# Schematic_Main_Board_backup.net
KiCad netlist of a schematic drawn in Altium Designer
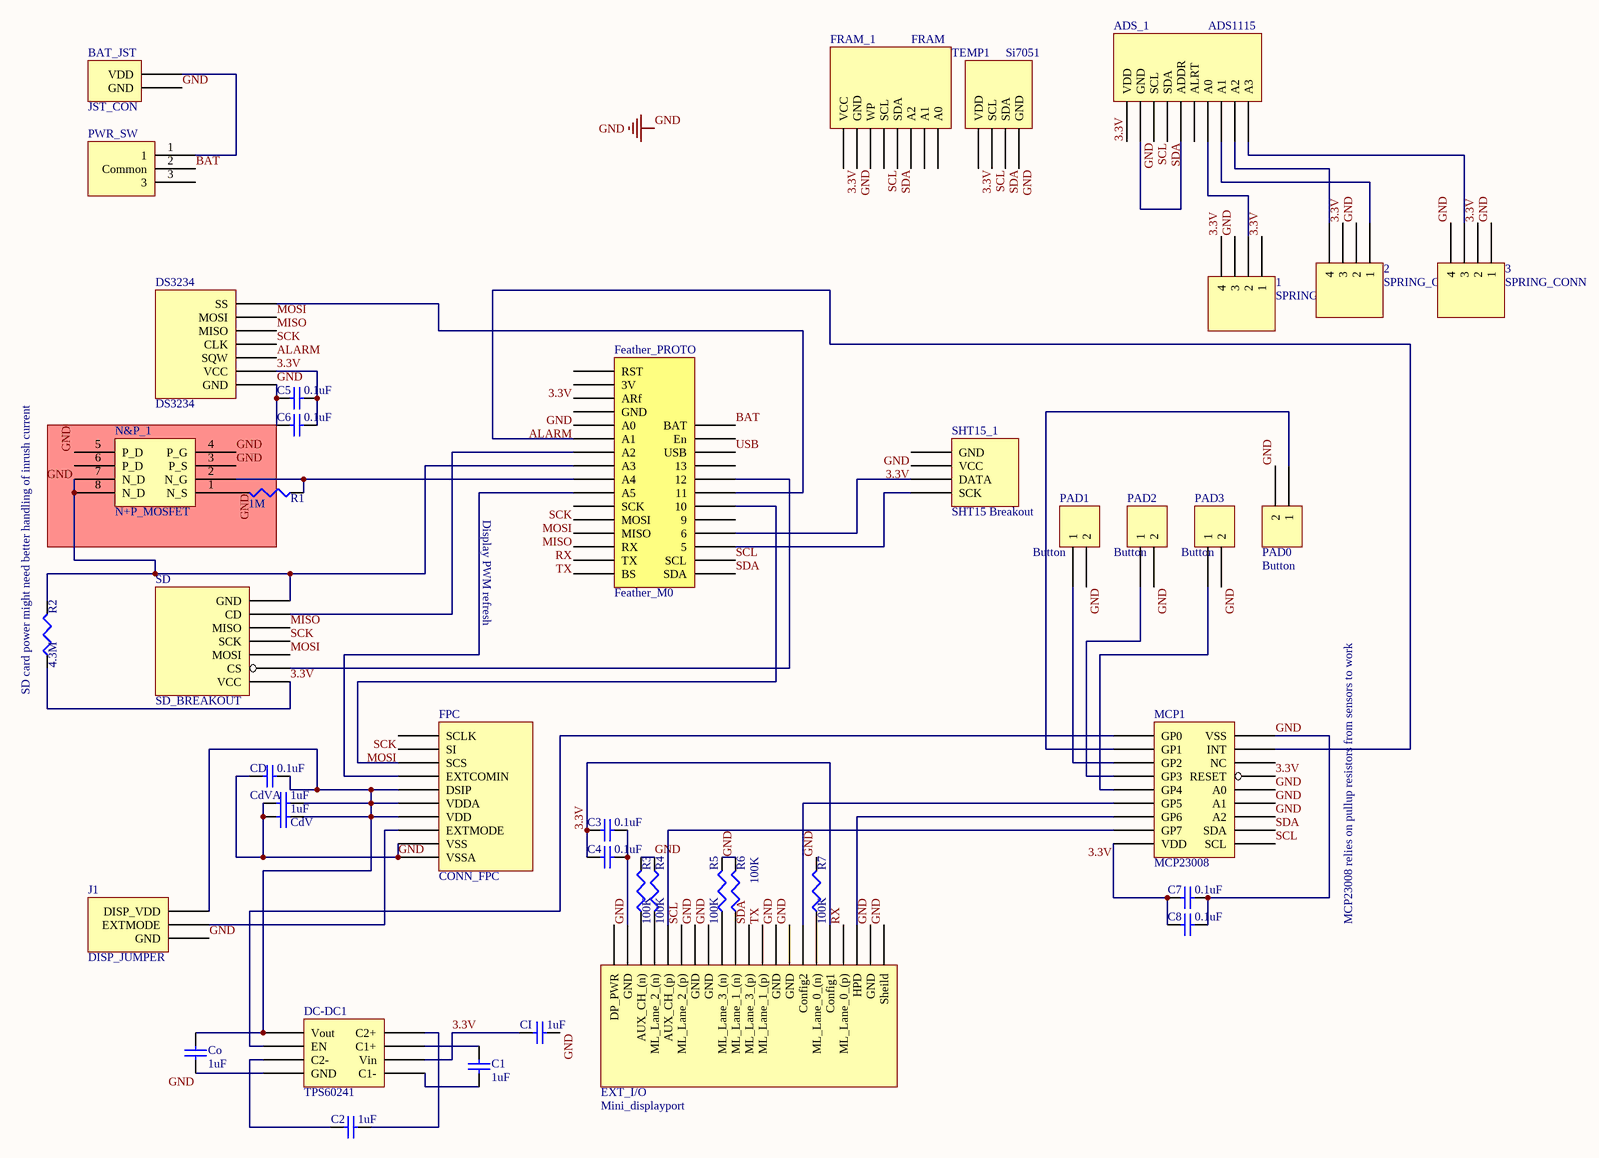
[diagram p0: Schematic_Main_Board_backup.SchDoc]

(export (version "E")
  (design (tool "Eeschema 10.0.6"))
  (components
    (comp (ref "1")
      (value "SPRING_CONN")
      (footprint "QUICK_CONN")
      (libsource (lib "Parts_Schematic") (part "SPRING_CONN"))
    )
    (comp (ref "2")
      (value "SPRING_CONN")
      (footprint "QUICK_CONN")
      (libsource (lib "Parts_Schematic") (part "SPRING_CONN"))
    )
    (comp (ref "3")
      (value "SPRING_CONN")
      (footprint "QUICK_CONN")
      (libsource (lib "Parts_Schematic") (part "SPRING_CONN"))
    )
    (comp (ref "ADS_1")
      (value "ADS1115")
      (footprint "ADS1115")
      (libsource (lib "Parts_Schematic") (part "ADS1115"))
    )
    (comp (ref "BAT_JST")
      (value "JST_CON")
      (footprint "JST_CONN")
      (libsource (lib "Parts_Schematic") (part "JST_CON"))
    )
    (comp (ref "C1")
      (value "1uF")
      (footprint "C0805")
      (description "Capacitor (Semiconductor SIM Model)")
      (fields (field (name "Comment") "Cap Semi") (field (name "PUBLISHER") "Altium Limited"))
      (libsource (lib "Miscellaneous Devices") (part "Cap Semi"))
    )
    (comp (ref "C2")
      (value "1uF")
      (footprint "C0805")
      (description "Capacitor (Semiconductor SIM Model)")
      (fields (field (name "Comment") "Cap Semi") (field (name "PUBLISHER") "Altium Limited"))
      (libsource (lib "Miscellaneous Devices") (part "Cap Semi"))
    )
    (comp (ref "C3")
      (value "0.1uF")
      (footprint "C0805")
      (description "Capacitor (Semiconductor SIM Model)")
      (fields (field (name "Comment") "Cap Semi") (field (name "PUBLISHER") "Altium Limited"))
      (libsource (lib "Miscellaneous Devices") (part "Cap Semi"))
    )
    (comp (ref "C4")
      (value "0.1uF")
      (footprint "C0805")
      (description "Capacitor (Semiconductor SIM Model)")
      (fields (field (name "Comment") "Cap Semi") (field (name "PUBLISHER") "Altium Limited"))
      (libsource (lib "Miscellaneous Devices") (part "Cap Semi"))
    )
    (comp (ref "C5")
      (value "0.1uF")
      (footprint "C0805")
      (description "Capacitor (Semiconductor SIM Model)")
      (fields (field (name "Comment") "Cap Semi") (field (name "PUBLISHER") "Altium Limited"))
      (libsource (lib "Miscellaneous Devices") (part "Cap Semi"))
    )
    (comp (ref "C6")
      (value "0.1uF")
      (footprint "C0805")
      (description "Capacitor (Semiconductor SIM Model)")
      (fields (field (name "Comment") "Cap Semi") (field (name "PUBLISHER") "Altium Limited"))
      (libsource (lib "Miscellaneous Devices") (part "Cap Semi"))
    )
    (comp (ref "C7")
      (value "0.1uF")
      (footprint "C0805")
      (description "Capacitor (Semiconductor SIM Model)")
      (fields (field (name "Comment") "Cap Semi") (field (name "PUBLISHER") "Altium Limited"))
      (libsource (lib "Miscellaneous Devices") (part "Cap Semi"))
    )
    (comp (ref "C8")
      (value "0.1uF")
      (footprint "C0805")
      (description "Capacitor (Semiconductor SIM Model)")
      (fields (field (name "Comment") "Cap Semi") (field (name "PUBLISHER") "Altium Limited"))
      (libsource (lib "Miscellaneous Devices") (part "Cap Semi"))
    )
    (comp (ref "CD")
      (value "0.1uF")
      (footprint "C0805")
      (description "Capacitor (Semiconductor SIM Model)")
      (fields (field (name "Comment") "Cap Semi") (field (name "PUBLISHER") "Altium Limited"))
      (libsource (lib "Miscellaneous Devices") (part "Cap Semi"))
    )
    (comp (ref "CdV")
      (value "1uF")
      (footprint "C0805")
      (description "Capacitor (Semiconductor SIM Model)")
      (fields (field (name "Comment") "Cap Semi") (field (name "PUBLISHER") "Altium Limited"))
      (libsource (lib "Miscellaneous Devices") (part "Cap Semi"))
    )
    (comp (ref "CdVA")
      (value "1uF")
      (footprint "C0805")
      (description "Capacitor (Semiconductor SIM Model)")
      (fields (field (name "Comment") "Cap Semi") (field (name "PUBLISHER") "Altium Limited"))
      (libsource (lib "Miscellaneous Devices") (part "Cap Semi"))
    )
    (comp (ref "CI")
      (value "1uF")
      (footprint "C0805")
      (description "Capacitor (Semiconductor SIM Model)")
      (fields (field (name "Comment") "Cap Semi") (field (name "PUBLISHER") "Altium Limited"))
      (libsource (lib "Miscellaneous Devices") (part "Cap Semi"))
    )
    (comp (ref "Co")
      (value "1uF")
      (footprint "C0805")
      (description "Capacitor (Semiconductor SIM Model)")
      (fields (field (name "Comment") "Cap Semi") (field (name "PUBLISHER") "Altium Limited"))
      (libsource (lib "Miscellaneous Devices") (part "Cap Semi"))
    )
    (comp (ref "DC-DC1")
      (value "TPS60241")
      (footprint "TPS60241")
      (libsource (lib "Parts_Schematic") (part "TPS60241"))
    )
    (comp (ref "DS3234")
      (value "DS3234")
      (footprint "DS3234_FOOTPRINT")
      (libsource (lib "Parts_Schematic") (part "DS3234"))
    )
    (comp (ref "EXT_I/O")
      (value "Mini_displayport")
      (footprint "CONN_Displayport")
      (libsource (lib "Parts_Schematic") (part "Mini_displayport"))
    )
    (comp (ref "Feather_PROTO")
      (value "Feather_M0")
      (footprint "Feather_M0")
      (libsource (lib "Parts_Schematic") (part "Feather_M0"))
    )
    (comp (ref "FPC")
      (value "CONN_FPC")
      (footprint "CONN_FPC")
      (libsource (lib "Parts_Schematic") (part "CONN_FPC"))
    )
    (comp (ref "FRAM_1") (value "FRAM") (footprint "FRAM") (libsource (lib "Parts_Schematic") (part "FRAM")))
    (comp (ref "J1")
      (value "DISP_JUMPER")
      (footprint "DISP_Jumper")
      (libsource (lib "Parts_Schematic") (part "DISP_JUMPER"))
    )
    (comp (ref "MCP1")
      (value "MCP23008")
      (footprint "MCP23008")
      (libsource (lib "Parts_Schematic") (part "MCP23008"))
    )
    (comp (ref "N&P_1")
      (value "N+P_MOSFET")
      (footprint "SOP8")
      (libsource (lib "Parts_Schematic") (part "N+P_MOSFET"))
    )
    (comp (ref "PAD0") (value "Button") (footprint "Button_footprint") (libsource (lib "") (part "Button_1")))
    (comp (ref "PAD1")
      (value "Button")
      (footprint "Button_footprint")
      (libsource (lib "Parts_Schematic") (part "Button"))
    )
    (comp (ref "PAD2")
      (value "Button")
      (footprint "Button_footprint")
      (libsource (lib "Parts_Schematic") (part "Button"))
    )
    (comp (ref "PAD3")
      (value "Button")
      (footprint "Button_footprint")
      (libsource (lib "Parts_Schematic") (part "Button"))
    )
    (comp (ref "PWR_SW")
      (value "Switch")
      (footprint "Switch_footprint")
      (libsource (lib "Parts_Schematic") (part "Switch"))
    )
    (comp (ref "R1")
      (value "1M")
      (footprint "6-0805_N")
      (description "Resistor")
      (fields (field (name "Comment") "Res3") (field (name "PUBLISHER") "Altium Limited"))
      (libsource (lib "Miscellaneous Devices") (part "Res3"))
    )
    (comp (ref "R2")
      (value "4.3M")
      (footprint "6-0805_N")
      (description "Resistor")
      (fields (field (name "Comment") "Res3") (field (name "PUBLISHER") "Altium Limited"))
      (libsource (lib "Miscellaneous Devices") (part "Res3"))
    )
    (comp (ref "R3")
      (value "100K")
      (footprint "6-0805_N")
      (description "Resistor")
      (fields (field (name "Comment") "Res3") (field (name "PUBLISHER") "Altium Limited"))
      (libsource (lib "Miscellaneous Devices") (part "Res3"))
    )
    (comp (ref "R4")
      (value "100K")
      (footprint "6-0805_N")
      (description "Resistor")
      (fields (field (name "Comment") "Res3") (field (name "PUBLISHER") "Altium Limited"))
      (libsource (lib "Miscellaneous Devices") (part "Res3"))
    )
    (comp (ref "R5")
      (value "100K")
      (footprint "6-0805_N")
      (description "Resistor")
      (fields (field (name "Comment") "Res3") (field (name "PUBLISHER") "Altium Limited"))
      (libsource (lib "Miscellaneous Devices") (part "Res3"))
    )
    (comp (ref "R6")
      (value "100K")
      (footprint "6-0805_N")
      (description "Resistor")
      (fields (field (name "Comment") "Res3") (field (name "PUBLISHER") "Altium Limited"))
      (libsource (lib "Miscellaneous Devices") (part "Res3"))
    )
    (comp (ref "R7")
      (value "100K")
      (footprint "6-0805_N")
      (description "Resistor")
      (fields (field (name "Comment") "Res3") (field (name "PUBLISHER") "Altium Limited"))
      (libsource (lib "Miscellaneous Devices") (part "Res3"))
    )
    (comp (ref "SD")
      (value "SD_BREAKOUT")
      (footprint "SD_BREAKOUT_FOOTPRINT")
      (libsource (lib "Parts_Schematic") (part "SD_BREAKOUT"))
    )
    (comp (ref "SHT15_1")
      (value "SHT15 Breakout")
      (footprint "SHT15_BREAKOUT_FOOTPRINT")
      (libsource (lib "Parts_Schematic") (part "SHT15_BREAKOUT"))
    )
    (comp (ref "TEMP1")
      (value "Si7051")
      (footprint "Si7051_Footprint")
      (libsource (lib "Parts_Schematic") (part "Si7051"))
    )
  )
  (nets
    (net (code "1") (name "/3.3V") (class "Default")
      (node (ref "1") (pin "1") (pinfunction "1_1") (pintype "passive"))
      (node (ref "1") (pin "4") (pinfunction "4_4") (pintype "passive"))
      (node (ref "2") (pin "3") (pinfunction "3_3") (pintype "passive"))
      (node (ref "3") (pin "2") (pinfunction "2_2") (pintype "passive"))
      (node (ref "ADS_1") (pin "1") (pinfunction "VDD_1") (pintype "passive"))
      (node (ref "C3") (pin "1") (pinfunction "1_1") (pintype "passive"))
      (node (ref "C4") (pin "2") (pinfunction "2_2") (pintype "passive"))
      (node (ref "C5") (pin "2") (pinfunction "2_2") (pintype "passive"))
      (node (ref "C6") (pin "1") (pinfunction "1_1") (pintype "passive"))
      (node (ref "C7") (pin "1") (pinfunction "1_1") (pintype "passive"))
      (node (ref "C8") (pin "2") (pinfunction "2_2") (pintype "passive"))
      (node (ref "CI") (pin "2") (pinfunction "2_2") (pintype "passive"))
      (node (ref "DC-DC1") (pin "6") (pinfunction "Vin_6") (pintype "passive"))
      (node (ref "DS3234") (pin "2") (pinfunction "VCC_2") (pintype "passive"))
      (node (ref "EXT_I/O") (pin "4") (pinfunction "Config1_4") (pintype "passive"))
      (node (ref "FRAM_1") (pin "1") (pinfunction "VCC_1") (pintype "passive"))
      (node (ref "Feather_PROTO") (pin "2") (pinfunction "3V_2") (pintype "passive"))
      (node (ref "MCP1") (pin "18") (pinfunction "VDD_18") (pintype "passive"))
      (node (ref "MCP1") (pin "6") (pinfunction "RESET_6") (pintype "passive"))
      (node (ref "R2") (pin "1") (pinfunction "1_1") (pintype "passive"))
      (node (ref "SD") (pin "1") (pinfunction "VCC_1") (pintype "passive"))
      (node (ref "SHT15_1") (pin "2") (pinfunction "VCC_2") (pintype "passive"))
      (node (ref "TEMP1") (pin "1") (pinfunction "VDD_1") (pintype "passive"))
    )
    (net (code "2") (name "/ALARM") (class "Default")
      (node (ref "DS3234") (pin "3") (pinfunction "SQW_3") (pintype "passive"))
      (node (ref "Feather_PROTO") (pin "5") (pinfunction "A0_5") (pintype "passive"))
    )
    (net (code "3") (name "/BAT") (class "Default")
      (node (ref "Feather_PROTO") (pin "28") (pinfunction "BAT_28") (pintype "passive"))
      (node (ref "PWR_SW") (pin "2") (pinfunction "Common_2") (pintype "passive"))
    )
    (net (code "4") (name "/MISO") (class "Default")
      (node (ref "DS3234") (pin "5") (pinfunction "MISO_5") (pintype "passive"))
      (node (ref "Feather_PROTO") (pin "13") (pinfunction "MISO_13") (pintype "passive"))
      (node (ref "SD") (pin "5") (pinfunction "MISO_5") (pintype "passive"))
    )
    (net (code "5") (name "/MOSI") (class "Default")
      (node (ref "DS3234") (pin "6") (pinfunction "MOSI_6") (pintype "passive"))
      (node (ref "FPC") (pin "2") (pinfunction "SI_2") (pintype "passive"))
      (node (ref "Feather_PROTO") (pin "12") (pinfunction "MOSI_12") (pintype "passive"))
      (node (ref "SD") (pin "3") (pinfunction "MOSI_3") (pintype "passive"))
    )
    (net (code "6") (name "/RX") (class "Default")
      (node (ref "EXT_I/O") (pin "3") (pinfunction "ML_Lane_0_(p)_3") (pintype "passive"))
      (node (ref "Feather_PROTO") (pin "14") (pinfunction "RX_14") (pintype "passive"))
    )
    (net (code "7") (name "/SCK") (class "Default")
      (node (ref "DS3234") (pin "4") (pinfunction "CLK_4") (pintype "passive"))
      (node (ref "FPC") (pin "1") (pinfunction "SCLK_1") (pintype "passive"))
      (node (ref "Feather_PROTO") (pin "11") (pinfunction "SCK_11") (pintype "passive"))
      (node (ref "SD") (pin "4") (pinfunction "SCK_4") (pintype "passive"))
    )
    (net (code "8") (name "/SCL") (class "Default")
      (node (ref "ADS_1") (pin "3") (pinfunction "SCL_3") (pintype "passive"))
      (node (ref "EXT_I/O") (pin "15") (pinfunction "ML_Lane_2_(p)_15") (pintype "passive"))
      (node (ref "FRAM_1") (pin "4") (pinfunction "SCL_4") (pintype "passive"))
      (node (ref "Feather_PROTO") (pin "18") (pinfunction "SCL_18") (pintype "passive"))
      (node (ref "MCP1") (pin "1") (pinfunction "SCL_1") (pintype "passive"))
      (node (ref "TEMP1") (pin "2") (pinfunction "SCL_2") (pintype "passive"))
    )
    (net (code "9") (name "/SDA") (class "Default")
      (node (ref "ADS_1") (pin "4") (pinfunction "SDA_4") (pintype "passive"))
      (node (ref "EXT_I/O") (pin "10") (pinfunction "ML_Lane_3_(p)_10") (pintype "passive"))
      (node (ref "FRAM_1") (pin "5") (pinfunction "SDA_5") (pintype "passive"))
      (node (ref "Feather_PROTO") (pin "17") (pinfunction "SDA_17") (pintype "passive"))
      (node (ref "MCP1") (pin "2") (pinfunction "SDA_2") (pintype "passive"))
      (node (ref "TEMP1") (pin "3") (pinfunction "SDA_3") (pintype "passive"))
    )
    (net (code "10") (name "/TX") (class "Default")
      (node (ref "EXT_I/O") (pin "9") (pinfunction "ML_Lane_1_(p)_9") (pintype "passive"))
      (node (ref "Feather_PROTO") (pin "15") (pinfunction "TX_15") (pintype "passive"))
    )
    (net (code "11") (name "/USB") (class "Default")
      (node (ref "Feather_PROTO") (pin "26") (pinfunction "USB_26") (pintype "passive"))
    )
    (net (code "12") (name "GND") (class "Default")
      (node (ref "1") (pin "3") (pinfunction "3_3") (pintype "passive"))
      (node (ref "2") (pin "2") (pinfunction "2_2") (pintype "passive"))
      (node (ref "3") (pin "1") (pinfunction "1_1") (pintype "passive"))
      (node (ref "3") (pin "4") (pinfunction "4_4") (pintype "passive"))
      (node (ref "ADS_1") (pin "2") (pinfunction "GND_2") (pintype "passive"))
      (node (ref "ADS_1") (pin "5") (pinfunction "ADDR_5") (pintype "passive"))
      (node (ref "BAT_JST") (pin "1") (pinfunction "GND_1") (pintype "passive"))
      (node (ref "C3") (pin "2") (pinfunction "2_2") (pintype "passive"))
      (node (ref "C4") (pin "1") (pinfunction "1_1") (pintype "passive"))
      (node (ref "C5") (pin "1") (pinfunction "1_1") (pintype "passive"))
      (node (ref "C6") (pin "2") (pinfunction "2_2") (pintype "passive"))
      (node (ref "C7") (pin "2") (pinfunction "2_2") (pintype "passive"))
      (node (ref "C8") (pin "1") (pinfunction "1_1") (pintype "passive"))
      (node (ref "CD") (pin "2") (pinfunction "2_2") (pintype "passive"))
      (node (ref "CI") (pin "1") (pinfunction "1_1") (pintype "passive"))
      (node (ref "CdV") (pin "2") (pinfunction "2_2") (pintype "passive"))
      (node (ref "CdVA") (pin "2") (pinfunction "2_2") (pintype "passive"))
      (node (ref "Co") (pin "2") (pinfunction "2_2") (pintype "passive"))
      (node (ref "DC-DC1") (pin "4") (pinfunction "GND_4") (pintype "passive"))
      (node (ref "DS3234") (pin "1") (pinfunction "GND_1") (pintype "passive"))
      (node (ref "EXT_I/O") (pin "0") (pinfunction "Sheild_0") (pintype "passive"))
      (node (ref "EXT_I/O") (pin "1") (pinfunction "GND_1") (pintype "passive"))
      (node (ref "EXT_I/O") (pin "13") (pinfunction "GND_13") (pintype "passive"))
      (node (ref "EXT_I/O") (pin "14") (pinfunction "GND_14") (pintype "passive"))
      (node (ref "EXT_I/O") (pin "19") (pinfunction "GND_19") (pintype "passive"))
      (node (ref "EXT_I/O") (pin "7") (pinfunction "GND_7") (pintype "passive"))
      (node (ref "EXT_I/O") (pin "8") (pinfunction "GND_8") (pintype "passive"))
      (node (ref "FPC") (pin "10") (pinfunction "VSSA_10") (pintype "passive"))
      (node (ref "FPC") (pin "9") (pinfunction "VSS_9") (pintype "passive"))
      (node (ref "FRAM_1") (pin "2") (pinfunction "GND_2") (pintype "passive"))
      (node (ref "Feather_PROTO") (pin "4") (pinfunction "GND_4") (pintype "passive"))
      (node (ref "J1") (pin "1") (pinfunction "GND_1") (pintype "passive"))
      (node (ref "MCP1") (pin "3") (pinfunction "A2_3") (pintype "passive"))
      (node (ref "MCP1") (pin "4") (pinfunction "A1_4") (pintype "passive"))
      (node (ref "MCP1") (pin "5") (pinfunction "A0_5") (pintype "passive"))
      (node (ref "MCP1") (pin "9") (pinfunction "VSS_9") (pintype "passive"))
      (node (ref "N&P_1") (pin "1") (pinfunction "N_S_1") (pintype "passive"))
      (node (ref "N&P_1") (pin "3") (pinfunction "P_S_3") (pintype "passive"))
      (node (ref "N&P_1") (pin "4") (pinfunction "P_G_4") (pintype "passive"))
      (node (ref "N&P_1") (pin "5") (pinfunction "P_D_5") (pintype "passive"))
      (node (ref "N&P_1") (pin "6") (pinfunction "P_D_6") (pintype "passive"))
      (node (ref "PAD0") (pin "2") (pinfunction "2_2") (pintype "passive"))
      (node (ref "PAD1") (pin "2") (pinfunction "2_2") (pintype "passive"))
      (node (ref "PAD2") (pin "2") (pinfunction "2_2") (pintype "passive"))
      (node (ref "PAD3") (pin "2") (pinfunction "2_2") (pintype "passive"))
      (node (ref "R1") (pin "2") (pinfunction "2_2") (pintype "passive"))
      (node (ref "R3") (pin "2") (pinfunction "2_2") (pintype "passive"))
      (node (ref "R4") (pin "1") (pinfunction "1_1") (pintype "passive"))
      (node (ref "R5") (pin "2") (pinfunction "2_2") (pintype "passive"))
      (node (ref "R6") (pin "2") (pinfunction "2_2") (pintype "passive"))
      (node (ref "R7") (pin "2") (pinfunction "2_2") (pintype "passive"))
      (node (ref "SHT15_1") (pin "1") (pinfunction "GND_1") (pintype "passive"))
      (node (ref "TEMP1") (pin "4") (pinfunction "GND_4") (pintype "passive"))
    )
    (net (code "13") (name "Net-(ADS_1-A0)") (class "Default")
      (node (ref "1") (pin "2") (pinfunction "2_2") (pintype "passive"))
      (node (ref "ADS_1") (pin "7") (pinfunction "A0_7") (pintype "passive"))
    )
    (net (code "14") (name "Net-(ADS_1-A1)") (class "Default")
      (node (ref "2") (pin "1") (pinfunction "1_1") (pintype "passive"))
      (node (ref "ADS_1") (pin "8") (pinfunction "A1_8") (pintype "passive"))
    )
    (net (code "15") (name "Net-(ADS_1-A2)") (class "Default")
      (node (ref "2") (pin "4") (pinfunction "4_4") (pintype "passive"))
      (node (ref "ADS_1") (pin "9") (pinfunction "A2_9") (pintype "passive"))
    )
    (net (code "16") (name "Net-(ADS_1-A3)") (class "Default")
      (node (ref "3") (pin "3") (pinfunction "3_3") (pintype "passive"))
      (node (ref "ADS_1") (pin "10") (pinfunction "A3_10") (pintype "passive"))
    )
    (net (code "17") (name "Net-(BAT_JST-VDD)") (class "Default")
      (node (ref "BAT_JST") (pin "2") (pinfunction "VDD_2") (pintype "passive"))
      (node (ref "PWR_SW") (pin "1") (pinfunction "1_1") (pintype "passive"))
    )
    (net (code "18") (name "Net-(DC-DC1-C1+)") (class "Default")
      (node (ref "C1") (pin "1") (pinfunction "1_1") (pintype "passive"))
      (node (ref "DC-DC1") (pin "7") (pinfunction "C1+_7") (pintype "passive"))
    )
    (net (code "19") (name "Net-(DC-DC1-C1-)") (class "Default")
      (node (ref "C1") (pin "2") (pinfunction "2_2") (pintype "passive"))
      (node (ref "DC-DC1") (pin "5") (pinfunction "C1-_5") (pintype "passive"))
    )
    (net (code "20") (name "Net-(DC-DC1-C2+)") (class "Default")
      (node (ref "C2") (pin "1") (pinfunction "1_1") (pintype "passive"))
      (node (ref "DC-DC1") (pin "8") (pinfunction "C2+_8") (pintype "passive"))
    )
    (net (code "21") (name "Net-(DC-DC1-C2-)") (class "Default")
      (node (ref "C2") (pin "2") (pinfunction "2_2") (pintype "passive"))
      (node (ref "DC-DC1") (pin "3") (pinfunction "C2-_3") (pintype "passive"))
    )
    (net (code "22") (name "Net-(DC-DC1-EN)") (class "Default")
      (node (ref "DC-DC1") (pin "2") (pinfunction "EN_2") (pintype "passive"))
      (node (ref "MCP1") (pin "10") (pinfunction "GP0_10") (pintype "passive"))
    )
    (net (code "23") (name "Net-(DC-DC1-Vout)") (class "Default")
      (node (ref "CD") (pin "1") (pinfunction "1_1") (pintype "passive"))
      (node (ref "CdV") (pin "1") (pinfunction "1_1") (pintype "passive"))
      (node (ref "CdVA") (pin "1") (pinfunction "1_1") (pintype "passive"))
      (node (ref "Co") (pin "1") (pinfunction "1_1") (pintype "passive"))
      (node (ref "DC-DC1") (pin "1") (pinfunction "Vout_1") (pintype "passive"))
      (node (ref "FPC") (pin "5") (pinfunction "DSIP_5") (pintype "passive"))
      (node (ref "FPC") (pin "6") (pinfunction "VDDA_6") (pintype "passive"))
      (node (ref "FPC") (pin "7") (pinfunction "VDD_7") (pintype "passive"))
      (node (ref "J1") (pin "3") (pinfunction "DISP_VDD_3") (pintype "passive"))
    )
    (net (code "24") (name "Net-(DS3234-SS)") (class "Default")
      (node (ref "DS3234") (pin "7") (pinfunction "SS_7") (pintype "passive"))
      (node (ref "Feather_PROTO") (pin "23") (pinfunction "11_23") (pintype "passive"))
    )
    (net (code "25") (name "Net-(EXT_I/O-AUX_CH_(n))") (class "Default")
      (node (ref "EXT_I/O") (pin "18") (pinfunction "AUX_CH_(n)_18") (pintype "passive"))
      (node (ref "R3") (pin "1") (pinfunction "1_1") (pintype "passive"))
    )
    (net (code "26") (name "Net-(EXT_I/O-AUX_CH_(p))") (class "Default")
      (node (ref "EXT_I/O") (pin "16") (pinfunction "AUX_CH_(p)_16") (pintype "passive"))
      (node (ref "MCP1") (pin "17") (pinfunction "GP7_17") (pintype "passive"))
    )
    (net (code "27") (name "Net-(EXT_I/O-Config2)") (class "Default")
      (node (ref "EXT_I/O") (pin "6") (pinfunction "Config2_6") (pintype "passive"))
      (node (ref "MCP1") (pin "15") (pinfunction "GP5_15") (pintype "passive"))
    )
    (net (code "28") (name "Net-(EXT_I/O-HPD)") (class "Default")
      (node (ref "EXT_I/O") (pin "2") (pinfunction "HPD_2") (pintype "passive"))
      (node (ref "MCP1") (pin "16") (pinfunction "GP6_16") (pintype "passive"))
    )
    (net (code "29") (name "Net-(EXT_I/O-ML_Lane_0_(n))") (class "Default")
      (node (ref "EXT_I/O") (pin "5") (pinfunction "ML_Lane_0_(n)_5") (pintype "passive"))
      (node (ref "R7") (pin "1") (pinfunction "1_1") (pintype "passive"))
    )
    (net (code "30") (name "Net-(EXT_I/O-ML_Lane_1_(n))") (class "Default")
      (node (ref "EXT_I/O") (pin "11") (pinfunction "ML_Lane_1_(n)_11") (pintype "passive"))
      (node (ref "R6") (pin "1") (pinfunction "1_1") (pintype "passive"))
    )
    (net (code "31") (name "Net-(EXT_I/O-ML_Lane_2_(n))") (class "Default")
      (node (ref "EXT_I/O") (pin "17") (pinfunction "ML_Lane_2_(n)_17") (pintype "passive"))
      (node (ref "R4") (pin "2") (pinfunction "2_2") (pintype "passive"))
    )
    (net (code "32") (name "Net-(EXT_I/O-ML_Lane_3_(n))") (class "Default")
      (node (ref "EXT_I/O") (pin "12") (pinfunction "ML_Lane_3_(n)_12") (pintype "passive"))
      (node (ref "R5") (pin "1") (pinfunction "1_1") (pintype "passive"))
    )
    (net (code "33") (name "Net-(FPC-EXTCOMIN)") (class "Default")
      (node (ref "FPC") (pin "4") (pinfunction "EXTCOMIN_4") (pintype "passive"))
      (node (ref "Feather_PROTO") (pin "10") (pinfunction "A5_10") (pintype "passive"))
    )
    (net (code "34") (name "Net-(FPC-EXTMODE)") (class "Default")
      (node (ref "FPC") (pin "8") (pinfunction "EXTMODE_8") (pintype "passive"))
      (node (ref "J1") (pin "2") (pinfunction "EXTMODE_2") (pintype "passive"))
    )
    (net (code "35") (name "Net-(FPC-SCS)") (class "Default")
      (node (ref "FPC") (pin "3") (pinfunction "SCS_3") (pintype "passive"))
      (node (ref "Feather_PROTO") (pin "22") (pinfunction "10_22") (pintype "passive"))
    )
    (net (code "36") (name "Net-(Feather_PROTO-5)") (class "Default")
      (node (ref "Feather_PROTO") (pin "19") (pinfunction "5_19") (pintype "passive"))
      (node (ref "SHT15_1") (pin "4") (pinfunction "SCK_4") (pintype "passive"))
    )
    (net (code "37") (name "Net-(Feather_PROTO-6)") (class "Default")
      (node (ref "Feather_PROTO") (pin "20") (pinfunction "6_20") (pintype "passive"))
      (node (ref "SHT15_1") (pin "3") (pinfunction "DATA_3") (pintype "passive"))
    )
    (net (code "38") (name "Net-(Feather_PROTO-12)") (class "Default")
      (node (ref "Feather_PROTO") (pin "24") (pinfunction "12_24") (pintype "passive"))
      (node (ref "SD") (pin "2") (pinfunction "CS_2") (pintype "passive"))
    )
    (net (code "39") (name "Net-(Feather_PROTO-A1)") (class "Default")
      (node (ref "Feather_PROTO") (pin "6") (pinfunction "A1_6") (pintype "passive"))
      (node (ref "MCP1") (pin "8") (pinfunction "INT_8") (pintype "passive"))
    )
    (net (code "40") (name "Net-(Feather_PROTO-A2)") (class "Default")
      (node (ref "Feather_PROTO") (pin "7") (pinfunction "A2_7") (pintype "passive"))
      (node (ref "SD") (pin "6") (pinfunction "CD_6") (pintype "passive"))
    )
    (net (code "41") (name "Net-(Feather_PROTO-A3)") (class "Default")
      (node (ref "Feather_PROTO") (pin "8") (pinfunction "A3_8") (pintype "passive"))
      (node (ref "N&P_1") (pin "7") (pinfunction "N_D_7") (pintype "passive"))
      (node (ref "N&P_1") (pin "8") (pinfunction "N_D_8") (pintype "passive"))
      (node (ref "R2") (pin "2") (pinfunction "2_2") (pintype "passive"))
      (node (ref "SD") (pin "7") (pinfunction "GND_7") (pintype "passive"))
    )
    (net (code "42") (name "Net-(Feather_PROTO-A4)") (class "Default")
      (node (ref "Feather_PROTO") (pin "9") (pinfunction "A4_9") (pintype "passive"))
      (node (ref "N&P_1") (pin "2") (pinfunction "N_G_2") (pintype "passive"))
      (node (ref "R1") (pin "1") (pinfunction "1_1") (pintype "passive"))
    )
    (net (code "43") (name "Net-(MCP1-GP1)") (class "Default")
      (node (ref "MCP1") (pin "11") (pinfunction "GP1_11") (pintype "passive"))
      (node (ref "PAD0") (pin "1") (pinfunction "1_1") (pintype "passive"))
    )
    (net (code "44") (name "Net-(MCP1-GP2)") (class "Default")
      (node (ref "MCP1") (pin "12") (pinfunction "GP2_12") (pintype "passive"))
      (node (ref "PAD1") (pin "1") (pinfunction "1_1") (pintype "passive"))
    )
    (net (code "45") (name "Net-(MCP1-GP3)") (class "Default")
      (node (ref "MCP1") (pin "13") (pinfunction "GP3_13") (pintype "passive"))
      (node (ref "PAD2") (pin "1") (pinfunction "1_1") (pintype "passive"))
    )
    (net (code "46") (name "Net-(MCP1-GP4)") (class "Default")
      (node (ref "MCP1") (pin "14") (pinfunction "GP4_14") (pintype "passive"))
      (node (ref "PAD3") (pin "1") (pinfunction "1_1") (pintype "passive"))
    )
    (net (code "47") (name "unconnected-(ADS_1-ALRT-Pad6)") (class "Default")
      (node (ref "ADS_1") (pin "6") (pinfunction "ALRT_6") (pintype "passive"))
    )
    (net (code "48") (name "unconnected-(EXT_I/O-DP_PWR-Pad20)") (class "Default")
      (node (ref "EXT_I/O") (pin "20") (pinfunction "DP_PWR_20") (pintype "passive"))
    )
    (net (code "49") (name "unconnected-(FRAM_1-A0-Pad8)") (class "Default")
      (node (ref "FRAM_1") (pin "8") (pinfunction "A0_8") (pintype "passive"))
    )
    (net (code "50") (name "unconnected-(FRAM_1-A1-Pad7)") (class "Default")
      (node (ref "FRAM_1") (pin "7") (pinfunction "A1_7") (pintype "passive"))
    )
    (net (code "51") (name "unconnected-(FRAM_1-A2-Pad6)") (class "Default")
      (node (ref "FRAM_1") (pin "6") (pinfunction "A2_6") (pintype "passive"))
    )
    (net (code "52") (name "unconnected-(FRAM_1-WP-Pad3)") (class "Default")
      (node (ref "FRAM_1") (pin "3") (pinfunction "WP_3") (pintype "passive"))
    )
    (net (code "53") (name "unconnected-(Feather_PROTO-9-Pad21)") (class "Default")
      (node (ref "Feather_PROTO") (pin "21") (pinfunction "9_21") (pintype "passive"))
    )
    (net (code "54") (name "unconnected-(Feather_PROTO-13-Pad25)") (class "Default")
      (node (ref "Feather_PROTO") (pin "25") (pinfunction "13_25") (pintype "passive"))
    )
    (net (code "55") (name "unconnected-(Feather_PROTO-ARf-Pad3)") (class "Default")
      (node (ref "Feather_PROTO") (pin "3") (pinfunction "ARf_3") (pintype "passive"))
    )
    (net (code "56") (name "unconnected-(Feather_PROTO-BS-Pad16)") (class "Default")
      (node (ref "Feather_PROTO") (pin "16") (pinfunction "BS_16") (pintype "passive"))
    )
    (net (code "57") (name "unconnected-(Feather_PROTO-En-Pad27)") (class "Default")
      (node (ref "Feather_PROTO") (pin "27") (pinfunction "En_27") (pintype "passive"))
    )
    (net (code "58") (name "unconnected-(Feather_PROTO-RST-Pad1)") (class "Default")
      (node (ref "Feather_PROTO") (pin "1") (pinfunction "RST_1") (pintype "passive"))
    )
    (net (code "59") (name "unconnected-(MCP1-NC-Pad7)") (class "Default")
      (node (ref "MCP1") (pin "7") (pinfunction "NC_7") (pintype "passive"))
    )
    (net (code "60") (name "unconnected-(PWR_SW-Pad3)") (class "Default")
      (node (ref "PWR_SW") (pin "3") (pinfunction "3_3") (pintype "passive"))
    )
  )
)
